# rasp_sheild_CAN.net
KiCad netlist of a schematic drawn in Altium Designer
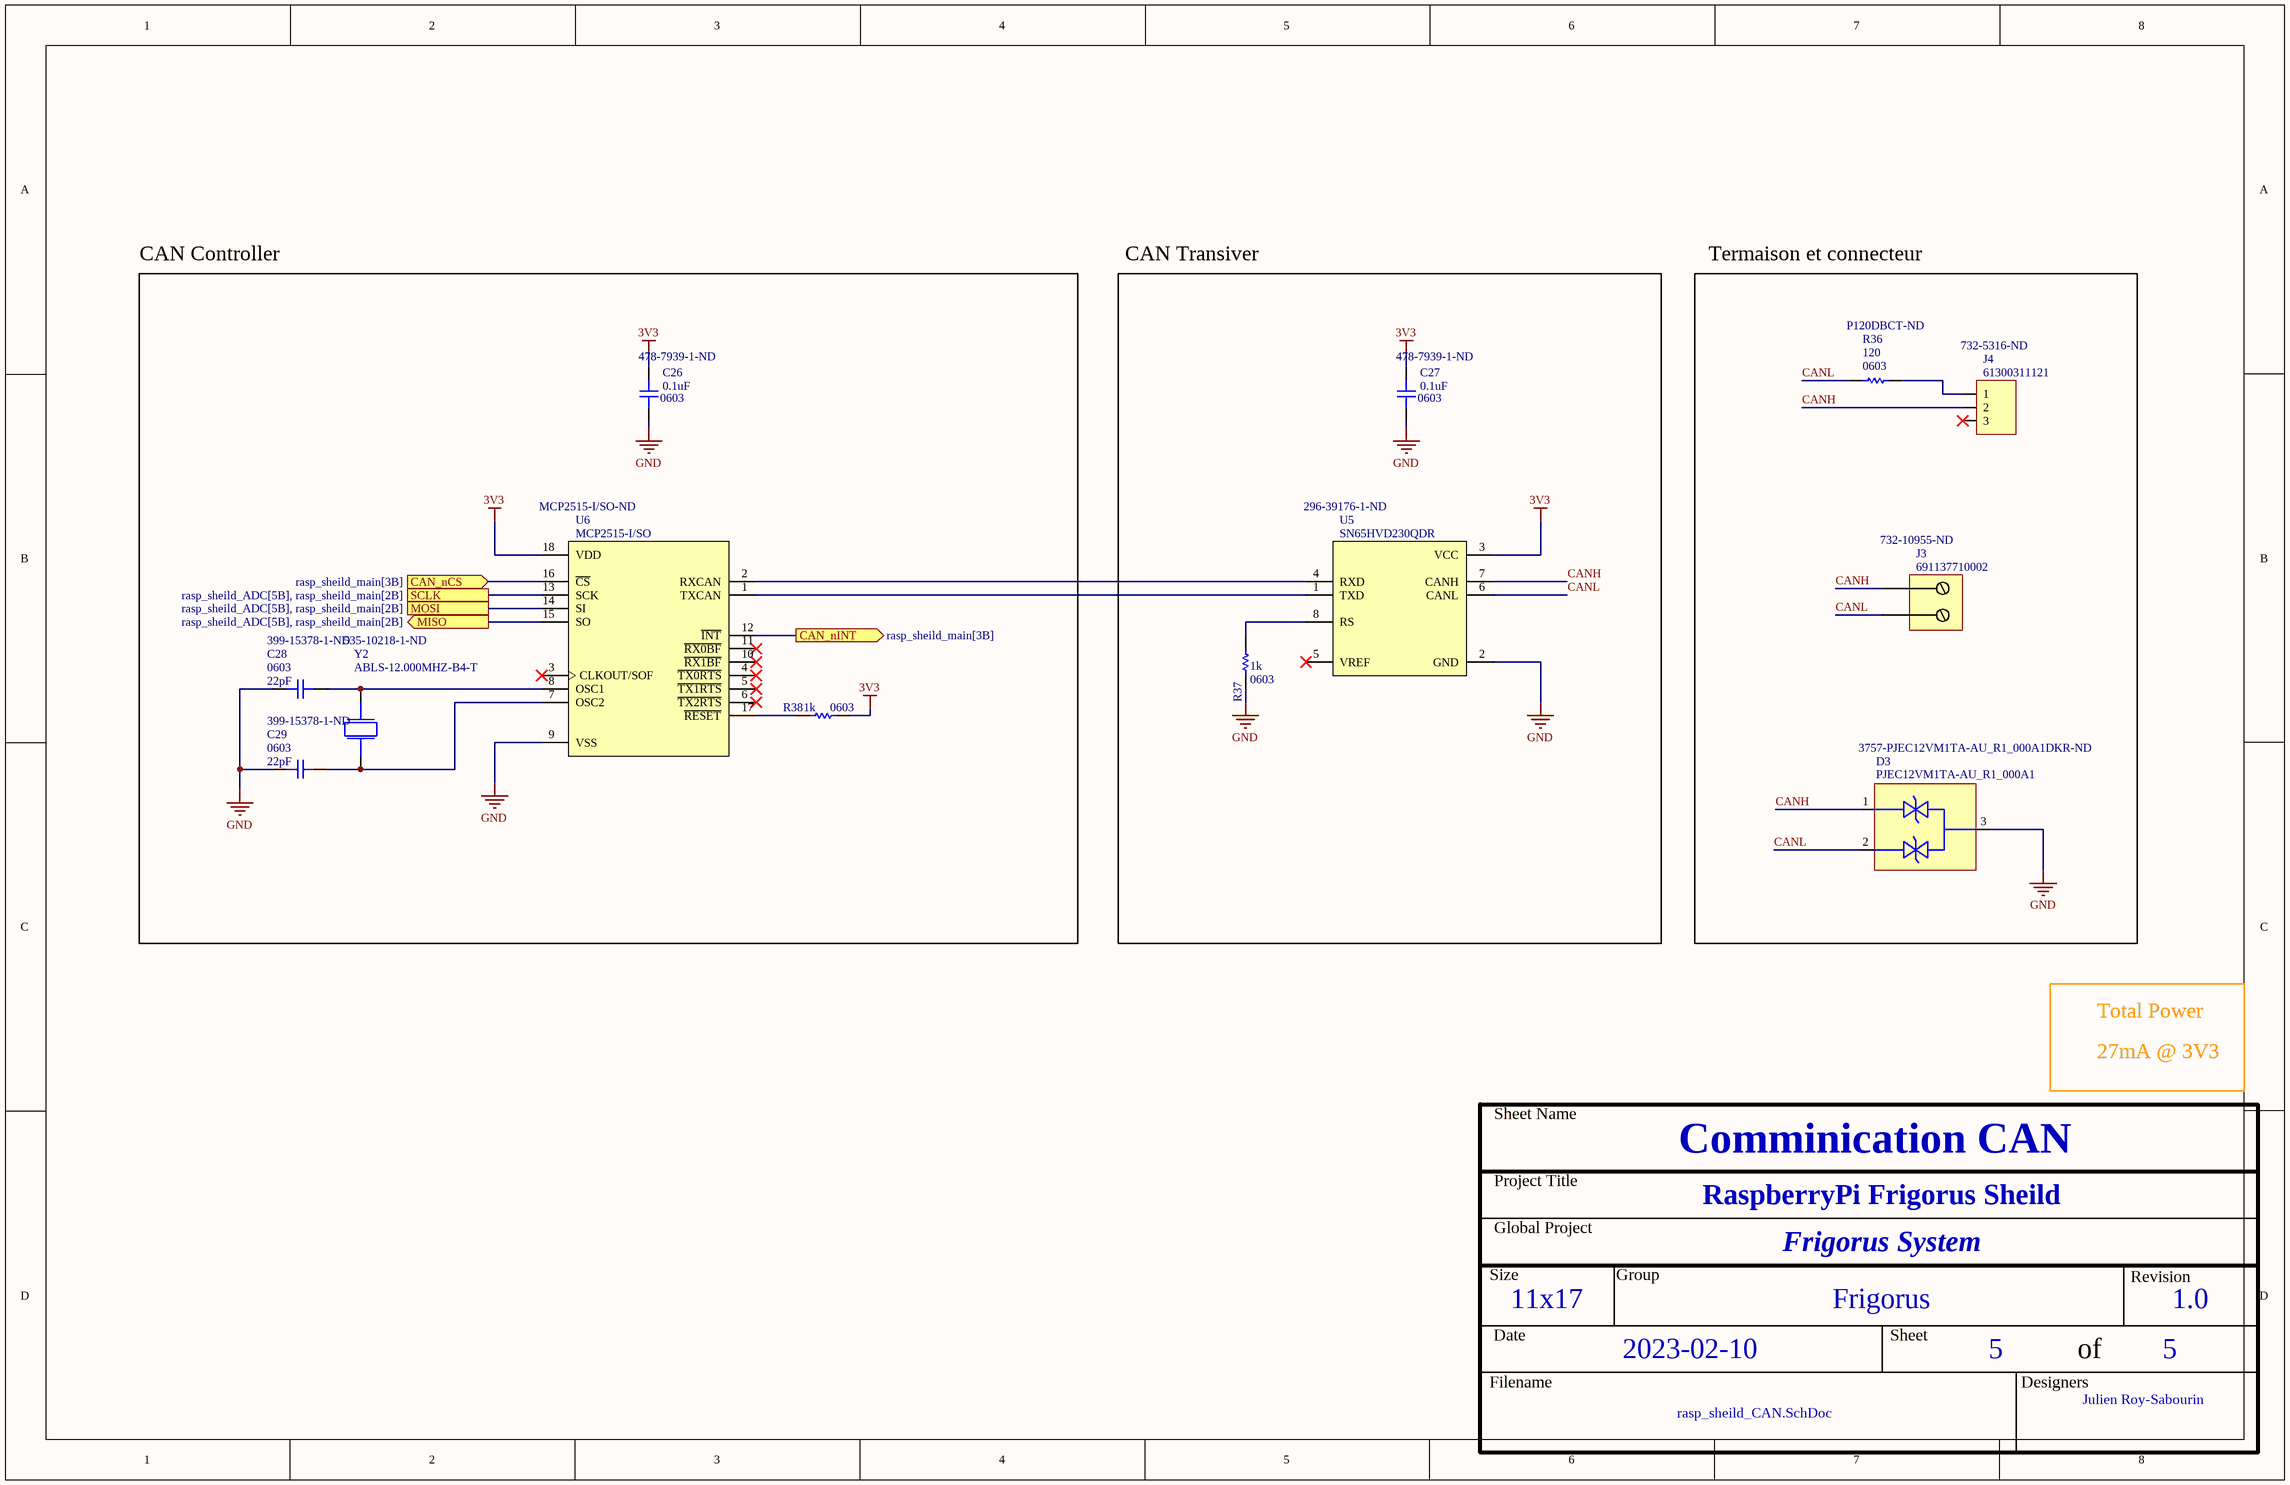
[diagram p0: rasp_sheild_CAN.SchDoc]

(export (version "E")
  (design (tool "Eeschema 10.0.6"))
  (components
    (comp (ref "C26")
      (value "0.1uF")
      (footprint "CAP_0603")
      (description "XXX - Description - Package")
      (fields
        (field (name "PACKAGE") "0603")
        (field (name "SUPPLIER PART NUMBER 1") "478-7939-1-ND")
        (field (name "Comment") "Part Number")
      )
      (libsource (lib "royj1311") (part "CAP_0603"))
    )
    (comp (ref "C27")
      (value "0.1uF")
      (footprint "CAP_0603")
      (description "XXX - Description - Package")
      (fields
        (field (name "PACKAGE") "0603")
        (field (name "SUPPLIER PART NUMBER 1") "478-7939-1-ND")
        (field (name "Comment") "Part Number")
      )
      (libsource (lib "royj1311") (part "CAP_0603"))
    )
    (comp (ref "C28")
      (value "22pF")
      (footprint "CAP_0603")
      (description "XXX - Description - Package")
      (fields
        (field (name "PACKAGE") "0603")
        (field (name "SUPPLIER PART NUMBER 1") "399-15378-1-ND")
        (field (name "Comment") "Part Number")
      )
      (libsource (lib "royj1311") (part "CAP_0603"))
    )
    (comp (ref "C29")
      (value "22pF")
      (footprint "CAP_0603")
      (description "XXX - Description - Package")
      (fields
        (field (name "PACKAGE") "0603")
        (field (name "SUPPLIER PART NUMBER 1") "399-15378-1-ND")
        (field (name "Comment") "Part Number")
      )
      (libsource (lib "royj1311") (part "CAP_0603"))
    )
    (comp (ref "D3")
      (value "PJEC12VM1TA-AU_R1_000A1")
      (footprint "SOT-23-3")
      (description "XXX - Description - Package")
      (fields (field (name "SUPPLIER PART NUMBER 1") "3757-PJEC12VM1TA-AU_R1_000A1DKR-ND"))
      (libsource (lib "royj1311") (part "PJEC12VM1TA-AU_R1_000A1"))
    )
    (comp (ref "J3")
      (value "691137710002")
      (footprint "691137710002")
      (description "2 Position Wire to Board Terminal Block Horizontal with Board 0.197\" (5.00mm) Through Hole")
      (fields (field (name "SUPPLIER PART NUMBER 1") "732-10955-ND"))
      (libsource (lib "royj1311") (part "691137710002"))
    )
    (comp (ref "J4")
      (value "61300311121")
      (footprint "61300311121")
      (description "Connector Header Through Hole 3 position 0.100\" (2.54mm)pr")
      (fields (field (name "SUPPLIER PART NUMBER 1") "732-5316-ND"))
      (libsource (lib "royj1311") (part "61300311121"))
    )
    (comp (ref "R36")
      (value "120")
      (footprint "RES_0603")
      (description "XXX - Description - Package")
      (fields
        (field (name "PACKAGE") "0603")
        (field (name "SUPPLIER PART NUMBER 1") "P120DBCT-ND")
        (field (name "Comment") "Part Number")
      )
      (libsource (lib "royj1311") (part "RES_0603"))
    )
    (comp (ref "R37")
      (value "1k")
      (footprint "RES_0603")
      (description "XXX - Description - Package")
      (fields (field (name "PACKAGE") "0603") (field (name "Comment") "Part Number"))
      (libsource (lib "royj1311") (part "RES_0603"))
    )
    (comp (ref "R38")
      (value "1k")
      (footprint "RES_0603")
      (description "XXX - Description - Package")
      (fields (field (name "PACKAGE") "0603") (field (name "Comment") "Part Number"))
      (libsource (lib "royj1311") (part "RES_0603"))
    )
    (comp (ref "U5")
      (value "SN65HVD230QDR")
      (footprint "8-SOIC")
      (description "1/1 Transceiver Half CANbus 8-SOIC")
      (fields (field (name "SUPPLIER PART NUMBER 1") "296-39176-1-ND"))
      (libsource (lib "royj1311") (part "SN65HVD230QDR"))
    )
    (comp (ref "U6")
      (value "MCP2515-I/SO")
      (footprint "18-SOIC")
      (description "CANbus Controller CAN 2.0 SPI Interface 18-SOIC")
      (fields (field (name "SUPPLIER PART NUMBER 1") "MCP2515-I/SO-ND"))
      (libsource (lib "royj1311") (part "MCP2515-I/SO"))
    )
    (comp (ref "Y2")
      (value "ABLS-12.000MHZ-B4-T")
      (footprint "ABLS-12.000MHZ-B4-T")
      (description "12 MHz ±30ppm Crystal 18pF 50 Ohms HC-49/US")
      (fields (field (name "SUPPLIER PART NUMBER 1") "535-10218-1-ND"))
      (libsource (lib "royj1311") (part "ABLS-12.000MHZ-B4-T"))
    )
  )
  (nets
    (net (code "1") (name "/CANH") (class "Default")
      (node (ref "D3") (pin "1") (pinfunction "1_1") (pintype "passive"))
      (node (ref "J3") (pin "1") (pinfunction "1_1") (pintype "passive"))
      (node (ref "J4") (pin "2") (pinfunction "2_2") (pintype "passive"))
      (node (ref "U5") (pin "7") (pinfunction "CANH_7") (pintype "passive"))
    )
    (net (code "2") (name "/CANL") (class "Default")
      (node (ref "D3") (pin "2") (pinfunction "2_2") (pintype "passive"))
      (node (ref "J3") (pin "2") (pinfunction "2_2") (pintype "passive"))
      (node (ref "R36") (pin "2") (pinfunction "2_2") (pintype "passive"))
      (node (ref "U5") (pin "6") (pinfunction "CANL_6") (pintype "passive"))
    )
    (net (code "3") (name "/CAN_nCS") (class "Default")
      (node (ref "U6") (pin "16") (pinfunction "~{CS}_16") (pintype "passive"))
    )
    (net (code "4") (name "/CAN_nINT") (class "Default")
      (node (ref "U6") (pin "12") (pinfunction "~{INT}_12") (pintype "passive"))
    )
    (net (code "5") (name "/MISO") (class "Default")
      (node (ref "U6") (pin "15") (pinfunction "SO_15") (pintype "passive"))
    )
    (net (code "6") (name "/MOSI") (class "Default")
      (node (ref "U6") (pin "14") (pinfunction "SI_14") (pintype "passive"))
    )
    (net (code "7") (name "/SCLK") (class "Default")
      (node (ref "U6") (pin "13") (pinfunction "SCK_13") (pintype "passive"))
    )
    (net (code "8") (name "3V3") (class "Default")
      (node (ref "C26") (pin "2") (pinfunction "2_2") (pintype "passive"))
      (node (ref "C27") (pin "2") (pinfunction "2_2") (pintype "passive"))
      (node (ref "R38") (pin "1") (pinfunction "1_1") (pintype "passive"))
      (node (ref "U5") (pin "3") (pinfunction "VCC_3") (pintype "passive"))
      (node (ref "U6") (pin "18") (pinfunction "VDD_18") (pintype "power_in"))
    )
    (net (code "9") (name "GND") (class "Default")
      (node (ref "C26") (pin "1") (pinfunction "1_1") (pintype "passive"))
      (node (ref "C27") (pin "1") (pinfunction "1_1") (pintype "passive"))
      (node (ref "C28") (pin "2") (pinfunction "2_2") (pintype "passive"))
      (node (ref "C29") (pin "2") (pinfunction "2_2") (pintype "passive"))
      (node (ref "D3") (pin "3") (pinfunction "3_3") (pintype "passive"))
      (node (ref "R37") (pin "2") (pinfunction "2_2") (pintype "passive"))
      (node (ref "U5") (pin "2") (pinfunction "GND_2") (pintype "passive"))
      (node (ref "U6") (pin "9") (pinfunction "VSS_9") (pintype "passive"))
    )
    (net (code "10") (name "Net-(J4-Pad1)") (class "Default")
      (node (ref "J4") (pin "1") (pinfunction "1_1") (pintype "passive"))
      (node (ref "R36") (pin "1") (pinfunction "1_1") (pintype "passive"))
    )
    (net (code "11") (name "Net-(U5-RS)") (class "Default")
      (node (ref "R37") (pin "1") (pinfunction "1_1") (pintype "passive"))
      (node (ref "U5") (pin "8") (pinfunction "RS_8") (pintype "passive"))
    )
    (net (code "12") (name "Net-(U5-RXD)") (class "Default")
      (node (ref "U5") (pin "4") (pinfunction "RXD_4") (pintype "passive"))
      (node (ref "U6") (pin "2") (pinfunction "RXCAN_2") (pintype "passive"))
    )
    (net (code "13") (name "Net-(U5-TXD)") (class "Default")
      (node (ref "U5") (pin "1") (pinfunction "TXD_1") (pintype "passive"))
      (node (ref "U6") (pin "1") (pinfunction "TXCAN_1") (pintype "passive"))
    )
    (net (code "14") (name "Net-(U6-OSC1)") (class "Default")
      (node (ref "C28") (pin "1") (pinfunction "1_1") (pintype "passive"))
      (node (ref "U6") (pin "8") (pinfunction "OSC1_8") (pintype "passive"))
      (node (ref "Y2") (pin "2") (pinfunction "2_2") (pintype "passive"))
    )
    (net (code "15") (name "Net-(U6-OSC2)") (class "Default")
      (node (ref "C29") (pin "1") (pinfunction "1_1") (pintype "passive"))
      (node (ref "U6") (pin "7") (pinfunction "OSC2_7") (pintype "passive"))
      (node (ref "Y2") (pin "1") (pinfunction "1_1") (pintype "passive"))
    )
    (net (code "16") (name "Net-(U6-~{RESET})") (class "Default")
      (node (ref "R38") (pin "2") (pinfunction "2_2") (pintype "passive"))
      (node (ref "U6") (pin "17") (pinfunction "~{RESET}_17") (pintype "passive"))
    )
    (net (code "17") (name "unconnected-(J4-Pad3)") (class "Default")
      (node (ref "J4") (pin "3") (pinfunction "3_3") (pintype "passive+no_connect"))
    )
    (net (code "18") (name "unconnected-(U5-VREF-Pad5)") (class "Default")
      (node (ref "U5") (pin "5") (pinfunction "VREF_5") (pintype "passive+no_connect"))
    )
    (net (code "19") (name "unconnected-(U6-CLKOUT{slash}SOF-Pad3)") (class "Default")
      (node (ref "U6") (pin "3") (pinfunction "CLKOUT/SOF_3") (pintype "passive+no_connect"))
    )
    (net (code "20") (name "unconnected-(U6-~{RX0BF}-Pad11)") (class "Default")
      (node (ref "U6") (pin "11") (pinfunction "~{RX0BF}_11") (pintype "passive+no_connect"))
    )
    (net (code "21") (name "unconnected-(U6-~{RX1BF}-Pad10)") (class "Default")
      (node (ref "U6") (pin "10") (pinfunction "~{RX1BF}_10") (pintype "passive+no_connect"))
    )
    (net (code "22") (name "unconnected-(U6-~{TX0RTS}-Pad4)") (class "Default")
      (node (ref "U6") (pin "4") (pinfunction "~{TX0RTS}_4") (pintype "passive+no_connect"))
    )
    (net (code "23") (name "unconnected-(U6-~{TX1RTS}-Pad5)") (class "Default")
      (node (ref "U6") (pin "5") (pinfunction "~{TX1RTS}_5") (pintype "passive+no_connect"))
    )
    (net (code "24") (name "unconnected-(U6-~{TX2RTS}-Pad6)") (class "Default")
      (node (ref "U6") (pin "6") (pinfunction "~{TX2RTS}_6") (pintype "passive+no_connect"))
    )
  )
)
